# CPLD.net
KiCad netlist of a schematic drawn in Altium Designer
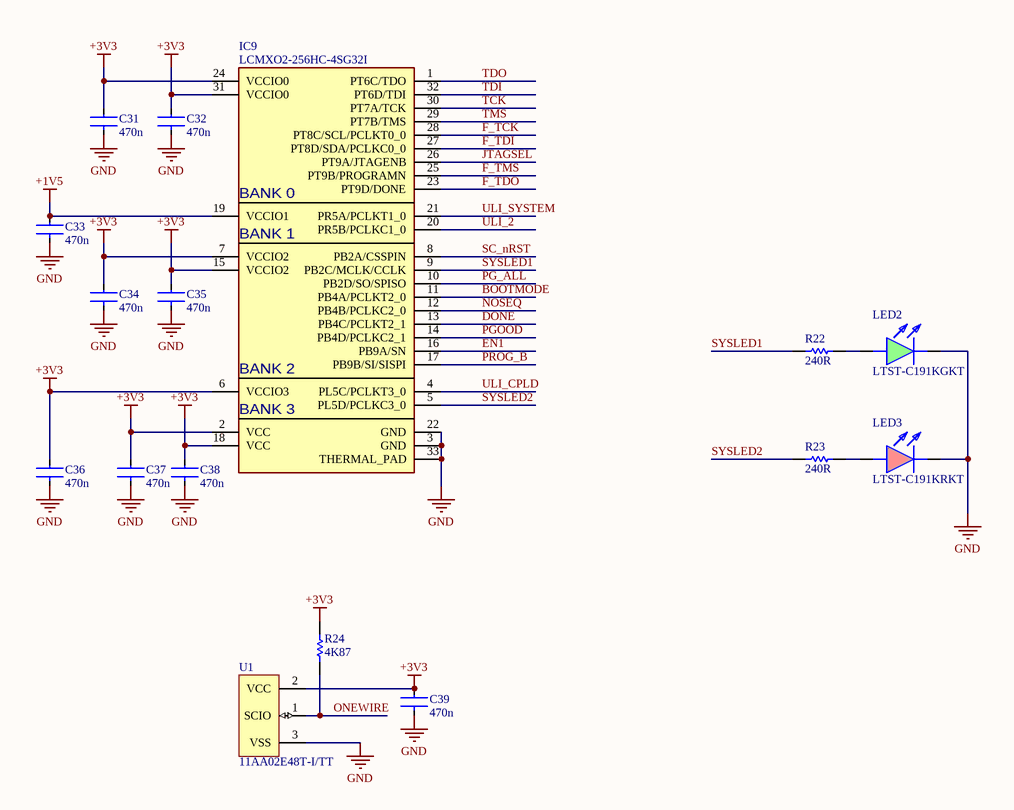
[diagram p0: CPLD.SchDoc]

(export (version "E")
  (design (tool "Eeschema 10.0.6"))
  (components
    (comp (ref "C31")
      (value "470n")
      (footprint "FP-C1005-050-0_05-IPC_B")
      (description "Multilayer Ceramic Capacitors 470nF ±10% 25V X5R SMD 0402")
      (fields (field (name "VOLTAGE") "25V") (field (name "TOLERANCE") "10%"))
      (libsource (lib "Altium Content Vault") (part "b4654b650e69147ec39a6b967a45e02"))
    )
    (comp (ref "C32")
      (value "470n")
      (footprint "FP-C1005-050-0_05-IPC_B")
      (description "Multilayer Ceramic Capacitors 470nF ±10% 25V X5R SMD 0402")
      (fields (field (name "VOLTAGE") "25V") (field (name "TOLERANCE") "10%"))
      (libsource (lib "Altium Content Vault") (part "b4654b650e69147ec39a6b967a45e02"))
    )
    (comp (ref "C33")
      (value "470n")
      (footprint "FP-C1005-050-0_05-IPC_B")
      (description "Multilayer Ceramic Capacitors 470nF ±10% 25V X5R SMD 0402")
      (fields (field (name "VOLTAGE") "25V") (field (name "TOLERANCE") "10%"))
      (libsource (lib "Altium Content Vault") (part "b4654b650e69147ec39a6b967a45e02"))
    )
    (comp (ref "C34")
      (value "470n")
      (footprint "FP-C1005-050-0_05-IPC_B")
      (description "Multilayer Ceramic Capacitors 470nF ±10% 25V X5R SMD 0402")
      (fields (field (name "VOLTAGE") "25V") (field (name "TOLERANCE") "10%"))
      (libsource (lib "Altium Content Vault") (part "b4654b650e69147ec39a6b967a45e02"))
    )
    (comp (ref "C35")
      (value "470n")
      (footprint "FP-C1005-050-0_05-IPC_B")
      (description "Multilayer Ceramic Capacitors 470nF ±10% 25V X5R SMD 0402")
      (fields (field (name "VOLTAGE") "25V") (field (name "TOLERANCE") "10%"))
      (libsource (lib "Altium Content Vault") (part "b4654b650e69147ec39a6b967a45e02"))
    )
    (comp (ref "C36")
      (value "470n")
      (footprint "FP-C1005-050-0_05-IPC_B")
      (description "Multilayer Ceramic Capacitors 470nF ±10% 25V X5R SMD 0402")
      (fields (field (name "VOLTAGE") "25V") (field (name "TOLERANCE") "10%"))
      (libsource (lib "Altium Content Vault") (part "b4654b650e69147ec39a6b967a45e02"))
    )
    (comp (ref "C37")
      (value "470n")
      (footprint "FP-C1005-050-0_05-IPC_B")
      (description "Multilayer Ceramic Capacitors 470nF ±10% 25V X5R SMD 0402")
      (fields (field (name "VOLTAGE") "25V") (field (name "TOLERANCE") "10%"))
      (libsource (lib "Altium Content Vault") (part "b4654b650e69147ec39a6b967a45e02"))
    )
    (comp (ref "C38")
      (value "470n")
      (footprint "FP-C1005-050-0_05-IPC_B")
      (description "Multilayer Ceramic Capacitors 470nF ±10% 25V X5R SMD 0402")
      (fields (field (name "VOLTAGE") "25V") (field (name "TOLERANCE") "10%"))
      (libsource (lib "Altium Content Vault") (part "b4654b650e69147ec39a6b967a45e02"))
    )
    (comp (ref "C39")
      (value "470n")
      (footprint "FP-C1005-050-0_05-IPC_B")
      (description "Multilayer Ceramic Capacitors 470nF ±10% 25V X5R SMD 0402")
      (fields (field (name "VOLTAGE") "25V") (field (name "TOLERANCE") "10%"))
      (libsource (lib "Altium Content Vault") (part "b4654b650e69147ec39a6b967a45e02"))
    )
    (comp (ref "IC9")
      (value "LCMXO2-256HC-4SG32I")
      (footprint "SamacSys:QFN50P500X500X60-33N")
      (description "Integrated Circuit")
      (fields (field (name "MOUSER PART NUMBER") "842-LCXO2256HC4SG32I"))
      (libsource (lib "SamacSys") (part "LCMXO2-256HC-4SG32I"))
    )
    (comp (ref "LED2")
      (value "LTST-C191KGKT")
      (footprint "SamacSys:LEDC1608X55N")
      (description "LED")
      (fields (field (name "MOUSER PART NUMBER") "859-LTST-C191KGKT"))
      (libsource (lib "SamacSys") (part "LTST-C191KGKT"))
    )
    (comp (ref "LED3")
      (value "LTST-C191KRKT")
      (footprint "SamacSys:LEDC1608X55N")
      (description "LED")
      (fields (field (name "MOUSER PART NUMBER") "859-LTST-C191KRKT"))
      (libsource (lib "SamacSys") (part "LTST-C191KRKT"))
    )
    (comp (ref "R22")
      (value "240R")
      (footprint "RESC0402(1005)_L")
      (description "240R 0.063W 1% 0402 (1005 Metric)  SMD")
      (fields (field (name "POWER") "0.063 W") (field (name "TOLERANCE") "1 %"))
      (libsource (lib "Altium Content Vault") (part "RES"))
    )
    (comp (ref "R23")
      (value "240R")
      (footprint "RESC0402(1005)_L")
      (description "240R 0.063W 1% 0402 (1005 Metric)  SMD")
      (fields (field (name "POWER") "0.063 W") (field (name "TOLERANCE") "1 %"))
      (libsource (lib "Altium Content Vault") (part "RES"))
    )
    (comp (ref "R24")
      (value "4K87")
      (footprint "RESC1005X40X25LL05T10")
      (fields (field (name "PART NUMBER") "RC0402FR-074K87L") (field (name "MANUFACTURER") "Yageo / Phycomp"))
      (libsource (lib "Altium Content Vault") (part "RES"))
    )
    (comp (ref "U1")
      (value "11AA02E48T-I/TT")
      (footprint "SOT-23-TT3_M")
      (libsource (lib "Altium Content Vault") (part "MEM-SEEPROM-11XXXX0-3"))
    )
  )
  (nets
    (net (code "1") (name "+1V5") (class "Default")
      (node (ref "C33") (pin "2") (pinfunction "2_2") (pintype "passive"))
      (node (ref "IC9") (pin "19") (pinfunction "VCCIO1_19") (pintype "passive"))
    )
    (net (code "2") (name "+3V3") (class "Default")
      (node (ref "C31") (pin "2") (pinfunction "2_2") (pintype "passive"))
      (node (ref "C32") (pin "2") (pinfunction "2_2") (pintype "passive"))
      (node (ref "C34") (pin "2") (pinfunction "2_2") (pintype "passive"))
      (node (ref "C35") (pin "2") (pinfunction "2_2") (pintype "passive"))
      (node (ref "C36") (pin "2") (pinfunction "2_2") (pintype "passive"))
      (node (ref "C37") (pin "2") (pinfunction "2_2") (pintype "passive"))
      (node (ref "C38") (pin "2") (pinfunction "2_2") (pintype "passive"))
      (node (ref "C39") (pin "2") (pinfunction "2_2") (pintype "passive"))
      (node (ref "IC9") (pin "15") (pinfunction "VCCIO2_15") (pintype "passive"))
      (node (ref "IC9") (pin "18") (pinfunction "VCC_18") (pintype "passive"))
      (node (ref "IC9") (pin "2") (pinfunction "VCC_2") (pintype "passive"))
      (node (ref "IC9") (pin "24") (pinfunction "VCCIO0_24") (pintype "passive"))
      (node (ref "IC9") (pin "31") (pinfunction "VCCIO0_31") (pintype "passive"))
      (node (ref "IC9") (pin "6") (pinfunction "VCCIO3_6") (pintype "passive"))
      (node (ref "IC9") (pin "7") (pinfunction "VCCIO2_7") (pintype "passive"))
      (node (ref "R24") (pin "1") (pinfunction "1_1") (pintype "passive"))
      (node (ref "U1") (pin "2") (pinfunction "VCC_2") (pintype "power_in"))
    )
    (net (code "3") (name "/BOOTMODE") (class "Default")
      (node (ref "IC9") (pin "11") (pinfunction "PB4A/PCLKT2_0_11") (pintype "passive"))
    )
    (net (code "4") (name "/DONE") (class "Default")
      (node (ref "IC9") (pin "13") (pinfunction "PB4C/PCLKT2_1_13") (pintype "passive"))
    )
    (net (code "5") (name "/EN1") (class "Default")
      (node (ref "IC9") (pin "16") (pinfunction "PB9A/SN_16") (pintype "passive"))
    )
    (net (code "6") (name "/F_TCK") (class "Default")
      (node (ref "IC9") (pin "28") (pinfunction "PT8C/SCL/PCLKT0_0_28") (pintype "passive"))
    )
    (net (code "7") (name "/F_TDI") (class "Default")
      (node (ref "IC9") (pin "27") (pinfunction "PT8D/SDA/PCLKC0_0_27") (pintype "passive"))
    )
    (net (code "8") (name "/F_TDO") (class "Default")
      (node (ref "IC9") (pin "23") (pinfunction "PT9D/DONE_23") (pintype "passive"))
    )
    (net (code "9") (name "/F_TMS") (class "Default")
      (node (ref "IC9") (pin "25") (pinfunction "PT9B/PROGRAMN_25") (pintype "passive"))
    )
    (net (code "10") (name "/JTAGSEL") (class "Default")
      (node (ref "IC9") (pin "26") (pinfunction "PT9A/JTAGENB_26") (pintype "passive"))
    )
    (net (code "11") (name "/NOSEQ") (class "Default")
      (node (ref "IC9") (pin "12") (pinfunction "PB4B/PCLKC2_0_12") (pintype "passive"))
    )
    (net (code "12") (name "/ONEWIRE") (class "Default")
      (node (ref "R24") (pin "2") (pinfunction "2_2") (pintype "passive"))
      (node (ref "U1") (pin "1") (pinfunction "SCIO_1") (pintype "bidirectional"))
    )
    (net (code "13") (name "/PGOOD") (class "Default")
      (node (ref "IC9") (pin "14") (pinfunction "PB4D/PCLKC2_1_14") (pintype "passive"))
    )
    (net (code "14") (name "/PG_ALL") (class "Default")
      (node (ref "IC9") (pin "10") (pinfunction "PB2D/SO/SPISO_10") (pintype "passive"))
    )
    (net (code "15") (name "/PROG_B") (class "Default")
      (node (ref "IC9") (pin "17") (pinfunction "PB9B/SI/SISPI_17") (pintype "passive"))
    )
    (net (code "16") (name "/SC_nRST") (class "Default")
      (node (ref "IC9") (pin "8") (pinfunction "PB2A/CSSPIN_8") (pintype "passive"))
    )
    (net (code "17") (name "/SYSLED1") (class "Default")
      (node (ref "IC9") (pin "9") (pinfunction "PB2C/MCLK/CCLK_9") (pintype "passive"))
      (node (ref "R22") (pin "2") (pinfunction "2_2") (pintype "passive"))
    )
    (net (code "18") (name "/SYSLED2") (class "Default")
      (node (ref "IC9") (pin "5") (pinfunction "PL5D/PCLKC3_0_5") (pintype "passive"))
      (node (ref "R23") (pin "2") (pinfunction "2_2") (pintype "passive"))
    )
    (net (code "19") (name "/TCK") (class "Default")
      (node (ref "IC9") (pin "30") (pinfunction "PT7A/TCK_30") (pintype "passive"))
    )
    (net (code "20") (name "/TDI") (class "Default")
      (node (ref "IC9") (pin "32") (pinfunction "PT6D/TDI_32") (pintype "passive"))
    )
    (net (code "21") (name "/TDO") (class "Default")
      (node (ref "IC9") (pin "1") (pinfunction "PT6C/TDO_1") (pintype "passive"))
    )
    (net (code "22") (name "/TMS") (class "Default")
      (node (ref "IC9") (pin "29") (pinfunction "PT7B/TMS_29") (pintype "passive"))
    )
    (net (code "23") (name "/ULI_2") (class "Default")
      (node (ref "IC9") (pin "20") (pinfunction "PR5B/PCLKC1_0_20") (pintype "passive"))
    )
    (net (code "24") (name "/ULI_CPLD") (class "Default")
      (node (ref "IC9") (pin "4") (pinfunction "PL5C/PCLKT3_0_4") (pintype "passive"))
    )
    (net (code "25") (name "/ULI_SYSTEM") (class "Default")
      (node (ref "IC9") (pin "21") (pinfunction "PR5A/PCLKT1_0_21") (pintype "passive"))
    )
    (net (code "26") (name "GND") (class "Default")
      (node (ref "C31") (pin "1") (pinfunction "1_1") (pintype "passive"))
      (node (ref "C32") (pin "1") (pinfunction "1_1") (pintype "passive"))
      (node (ref "C33") (pin "1") (pinfunction "1_1") (pintype "passive"))
      (node (ref "C34") (pin "1") (pinfunction "1_1") (pintype "passive"))
      (node (ref "C35") (pin "1") (pinfunction "1_1") (pintype "passive"))
      (node (ref "C36") (pin "1") (pinfunction "1_1") (pintype "passive"))
      (node (ref "C37") (pin "1") (pinfunction "1_1") (pintype "passive"))
      (node (ref "C38") (pin "1") (pinfunction "1_1") (pintype "passive"))
      (node (ref "C39") (pin "1") (pinfunction "1_1") (pintype "passive"))
      (node (ref "IC9") (pin "22") (pinfunction "GND_22") (pintype "passive"))
      (node (ref "IC9") (pin "3") (pinfunction "GND_3") (pintype "passive"))
      (node (ref "IC9") (pin "33") (pinfunction "THERMAL_PAD_33") (pintype "passive"))
      (node (ref "LED2") (pin "1") (pinfunction "K_1") (pintype "passive"))
      (node (ref "LED3") (pin "1") (pinfunction "K_1") (pintype "passive"))
      (node (ref "U1") (pin "3") (pinfunction "VSS_3") (pintype "power_in"))
    )
    (net (code "27") (name "Net-(LED2-A)") (class "Default")
      (node (ref "LED2") (pin "2") (pinfunction "A_2") (pintype "passive"))
      (node (ref "R22") (pin "1") (pinfunction "1_1") (pintype "passive"))
    )
    (net (code "28") (name "Net-(LED3-A)") (class "Default")
      (node (ref "LED3") (pin "2") (pinfunction "A_2") (pintype "passive"))
      (node (ref "R23") (pin "1") (pinfunction "1_1") (pintype "passive"))
    )
  )
)
